# DRL_Circuit.net
KiCad netlist of a schematic drawn in Altium Designer
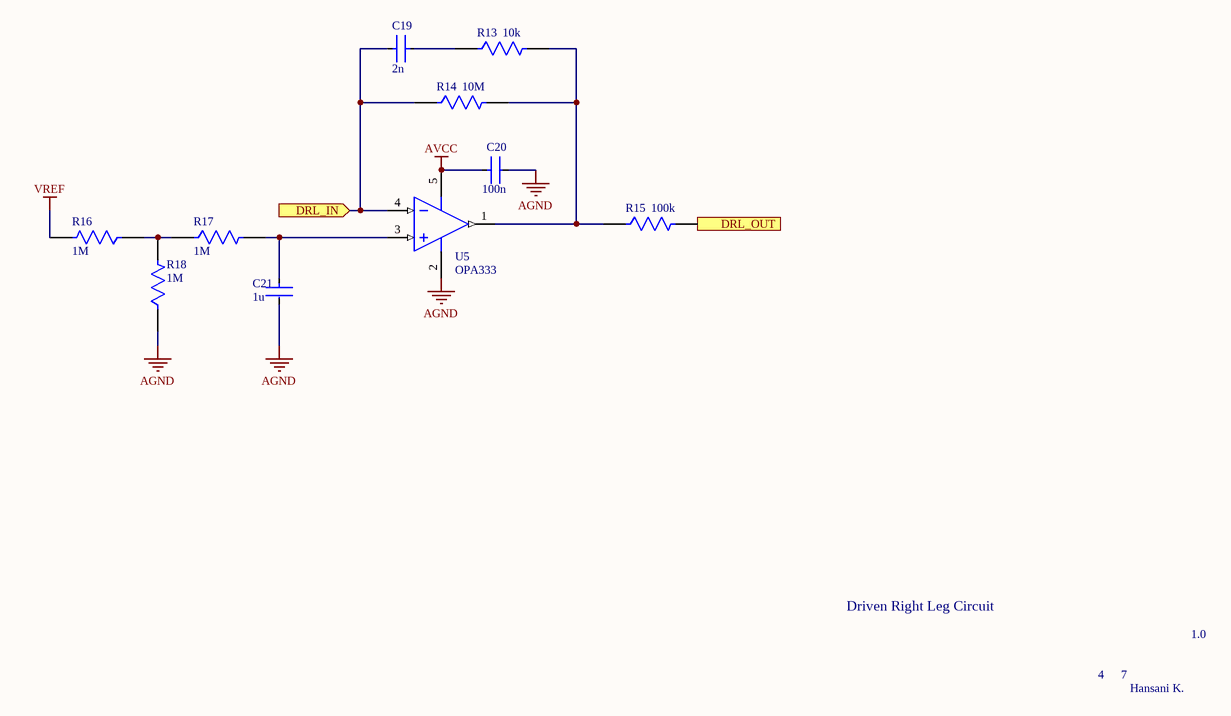
[diagram p0: DRL_Circuit.SchDoc]

(export (version "E")
  (design (tool "Eeschema 10.0.6"))
  (components
    (comp (ref "C19")
      (value "2n")
      (footprint "PCBComponent_1")
      (description "Cap Ceramic 0.002uF 100V X7R 5% SMD 0805 125°C T/R")
      (fields
        (field (name "MANUFACTURER") "KYOCERA AVX")
        (field (name "MANUFACTURER PART NUMBER") "08051C202JAT2A")
      )
      (libsource (lib "Schlib1") (part "08051C202JAT2A"))
    )
    (comp (ref "C20")
      (value "100n")
      (footprint "FP-GRM155-0_05-MFG")
      (description "Chip Multilayer Ceramic Capacitors for General Purpose, 0402, 0.10uF, B, 10%, 20%, 50V")
      (libsource (lib "Altium Content Vault") (part "02cd4be3c70576c341d710602a673aa"))
    )
    (comp (ref "C21")
      (value "1u")
      (footprint "FP-0603-L_1_6_0_15-W_0_81-IPC_A")
      (description "General Purpose Ceramic Capacitor, 0603, 1uF, 10%, X5R, 15%, 6.3V")
      (fields (field (name "VOLTAGE") "6.3V") (field (name "TOLERANCE") "10%"))
      (libsource (lib "Altium Content Vault") (part "02cd4be3c70576c341d710602a673aa"))
    )
    (comp (ref "R13")
      (value "10k")
      (footprint "PCBComponent_1")
      (description "ERJ Thick Film Chip Resistor 0805 350K Ohm 5% 0.125 W 2-Pin Surface Mount Punched Carrier T/R")
      (fields
        (field (name "MANUFACTURER") "Panasonic")
        (field (name "MANUFACTURER PART NUMBER") "ERJ-6GEYJ354V")
      )
      (libsource (lib "Schlib1") (part "ERJ-6GEYJ354V"))
    )
    (comp (ref "R14")
      (value "10M")
      (footprint "PCBComponent_1")
      (description "ERJ Thick Film Chip Resistor 0805 350K Ohm 5% 0.125 W 2-Pin Surface Mount Punched Carrier T/R")
      (fields
        (field (name "MANUFACTURER") "Panasonic")
        (field (name "MANUFACTURER PART NUMBER") "ERJ-6GEYJ354V")
      )
      (libsource (lib "Schlib1") (part "ERJ-6GEYJ354V"))
    )
    (comp (ref "R15")
      (value "100k")
      (footprint "PCBComponent_1")
      (description "ERJ Thick Film Chip Resistor 0805 350K Ohm 5% 0.125 W 2-Pin Surface Mount Punched Carrier T/R")
      (fields
        (field (name "MANUFACTURER") "Panasonic")
        (field (name "MANUFACTURER PART NUMBER") "ERJ-6GEYJ354V")
      )
      (libsource (lib "Schlib1") (part "ERJ-6GEYJ354V"))
    )
    (comp (ref "R16")
      (value "1M")
      (footprint "PCBComponent_1")
      (description "ERJ Thick Film Chip Resistor 0805 350K Ohm 5% 0.125 W 2-Pin Surface Mount Punched Carrier T/R")
      (fields
        (field (name "MANUFACTURER") "Panasonic")
        (field (name "MANUFACTURER PART NUMBER") "ERJ-6GEYJ354V")
      )
      (libsource (lib "Schlib1") (part "ERJ-6GEYJ354V"))
    )
    (comp (ref "R17")
      (value "1M")
      (footprint "FP-RK73H2A-IPC_A")
      (description "1MΩ ±1% 0.25W Chip Resistor 0805 Thick Film AEC-Q200 Qualified")
      (fields (field (name "TOLERANCE") "1%"))
      (libsource (lib "Altium Content Vault") (part "1029c3af85768c4190bb7ad29bc67b5"))
    )
    (comp (ref "R18")
      (value "1M")
      (footprint "PCBComponent_1")
      (description "ERJ Thick Film Chip Resistor 0805 350K Ohm 5% 0.125 W 2-Pin Surface Mount Punched Carrier T/R")
      (fields
        (field (name "MANUFACTURER") "Panasonic")
        (field (name "MANUFACTURER PART NUMBER") "ERJ-6GEYJ354V")
      )
      (libsource (lib "Schlib1") (part "ERJ-6GEYJ354V"))
    )
    (comp (ref "U5")
      (value "OPA333")
      (footprint "DBV0005A_M")
      (fields (field (name "PARTNUMBER") "OPA333AIDBVT") (field (name "MANUFACTURER") "Texas Instruments"))
      (libsource (lib "Altium Content Vault") (part "TI-OPA_SM7XXXX-DBV5"))
    )
  )
  (nets
    (net (code "1") (name "/DRL_IN") (class "Default")
      (node (ref "C19") (pin "1") (pinfunction "1_1") (pintype "passive"))
      (node (ref "R14") (pin "1") (pinfunction "1_1") (pintype "passive"))
      (node (ref "U5") (pin "4") (pinfunction "IN-_4") (pintype "input"))
    )
    (net (code "2") (name "/DRL_OUT") (class "Default")
      (node (ref "R15") (pin "2") (pinfunction "2_2") (pintype "passive"))
    )
    (net (code "3") (name "AGND") (class "Default")
      (node (ref "C20") (pin "2") (pinfunction "2_2") (pintype "passive"))
      (node (ref "C21") (pin "2") (pinfunction "2_2") (pintype "passive"))
      (node (ref "R18") (pin "1") (pinfunction "1_1") (pintype "passive"))
      (node (ref "U5") (pin "2") (pinfunction "V-_2") (pintype "power_in"))
    )
    (net (code "4") (name "AVCC") (class "Default")
      (node (ref "C20") (pin "1") (pinfunction "1_1") (pintype "passive"))
      (node (ref "U5") (pin "5") (pinfunction "V+_5") (pintype "power_in"))
    )
    (net (code "5") (name "Net-(C19-Pad2)") (class "Default")
      (node (ref "C19") (pin "2") (pinfunction "2_2") (pintype "passive"))
      (node (ref "R13") (pin "1") (pinfunction "1_1") (pintype "passive"))
    )
    (net (code "6") (name "Net-(R16-Pad1)") (class "Default")
      (node (ref "R16") (pin "1") (pinfunction "1_1") (pintype "passive"))
      (node (ref "R17") (pin "1") (pinfunction "1_1") (pintype "passive"))
      (node (ref "R18") (pin "2") (pinfunction "2_2") (pintype "passive"))
    )
    (net (code "7") (name "Net-(U5-IN+)") (class "Default")
      (node (ref "C21") (pin "1") (pinfunction "1_1") (pintype "passive"))
      (node (ref "R17") (pin "2") (pinfunction "2_2") (pintype "passive"))
      (node (ref "U5") (pin "3") (pinfunction "IN+_3") (pintype "input"))
    )
    (net (code "8") (name "Net-(U5-OUT)") (class "Default")
      (node (ref "R13") (pin "2") (pinfunction "2_2") (pintype "passive"))
      (node (ref "R14") (pin "2") (pinfunction "2_2") (pintype "passive"))
      (node (ref "R15") (pin "1") (pinfunction "1_1") (pintype "passive"))
      (node (ref "U5") (pin "1") (pinfunction "OUT_1") (pintype "output"))
    )
    (net (code "9") (name "VREF") (class "Default")
      (node (ref "R16") (pin "2") (pinfunction "2_2") (pintype "passive"))
    )
  )
)
